# electronic_load.net
KiCad netlist of a schematic drawn in EAGLE
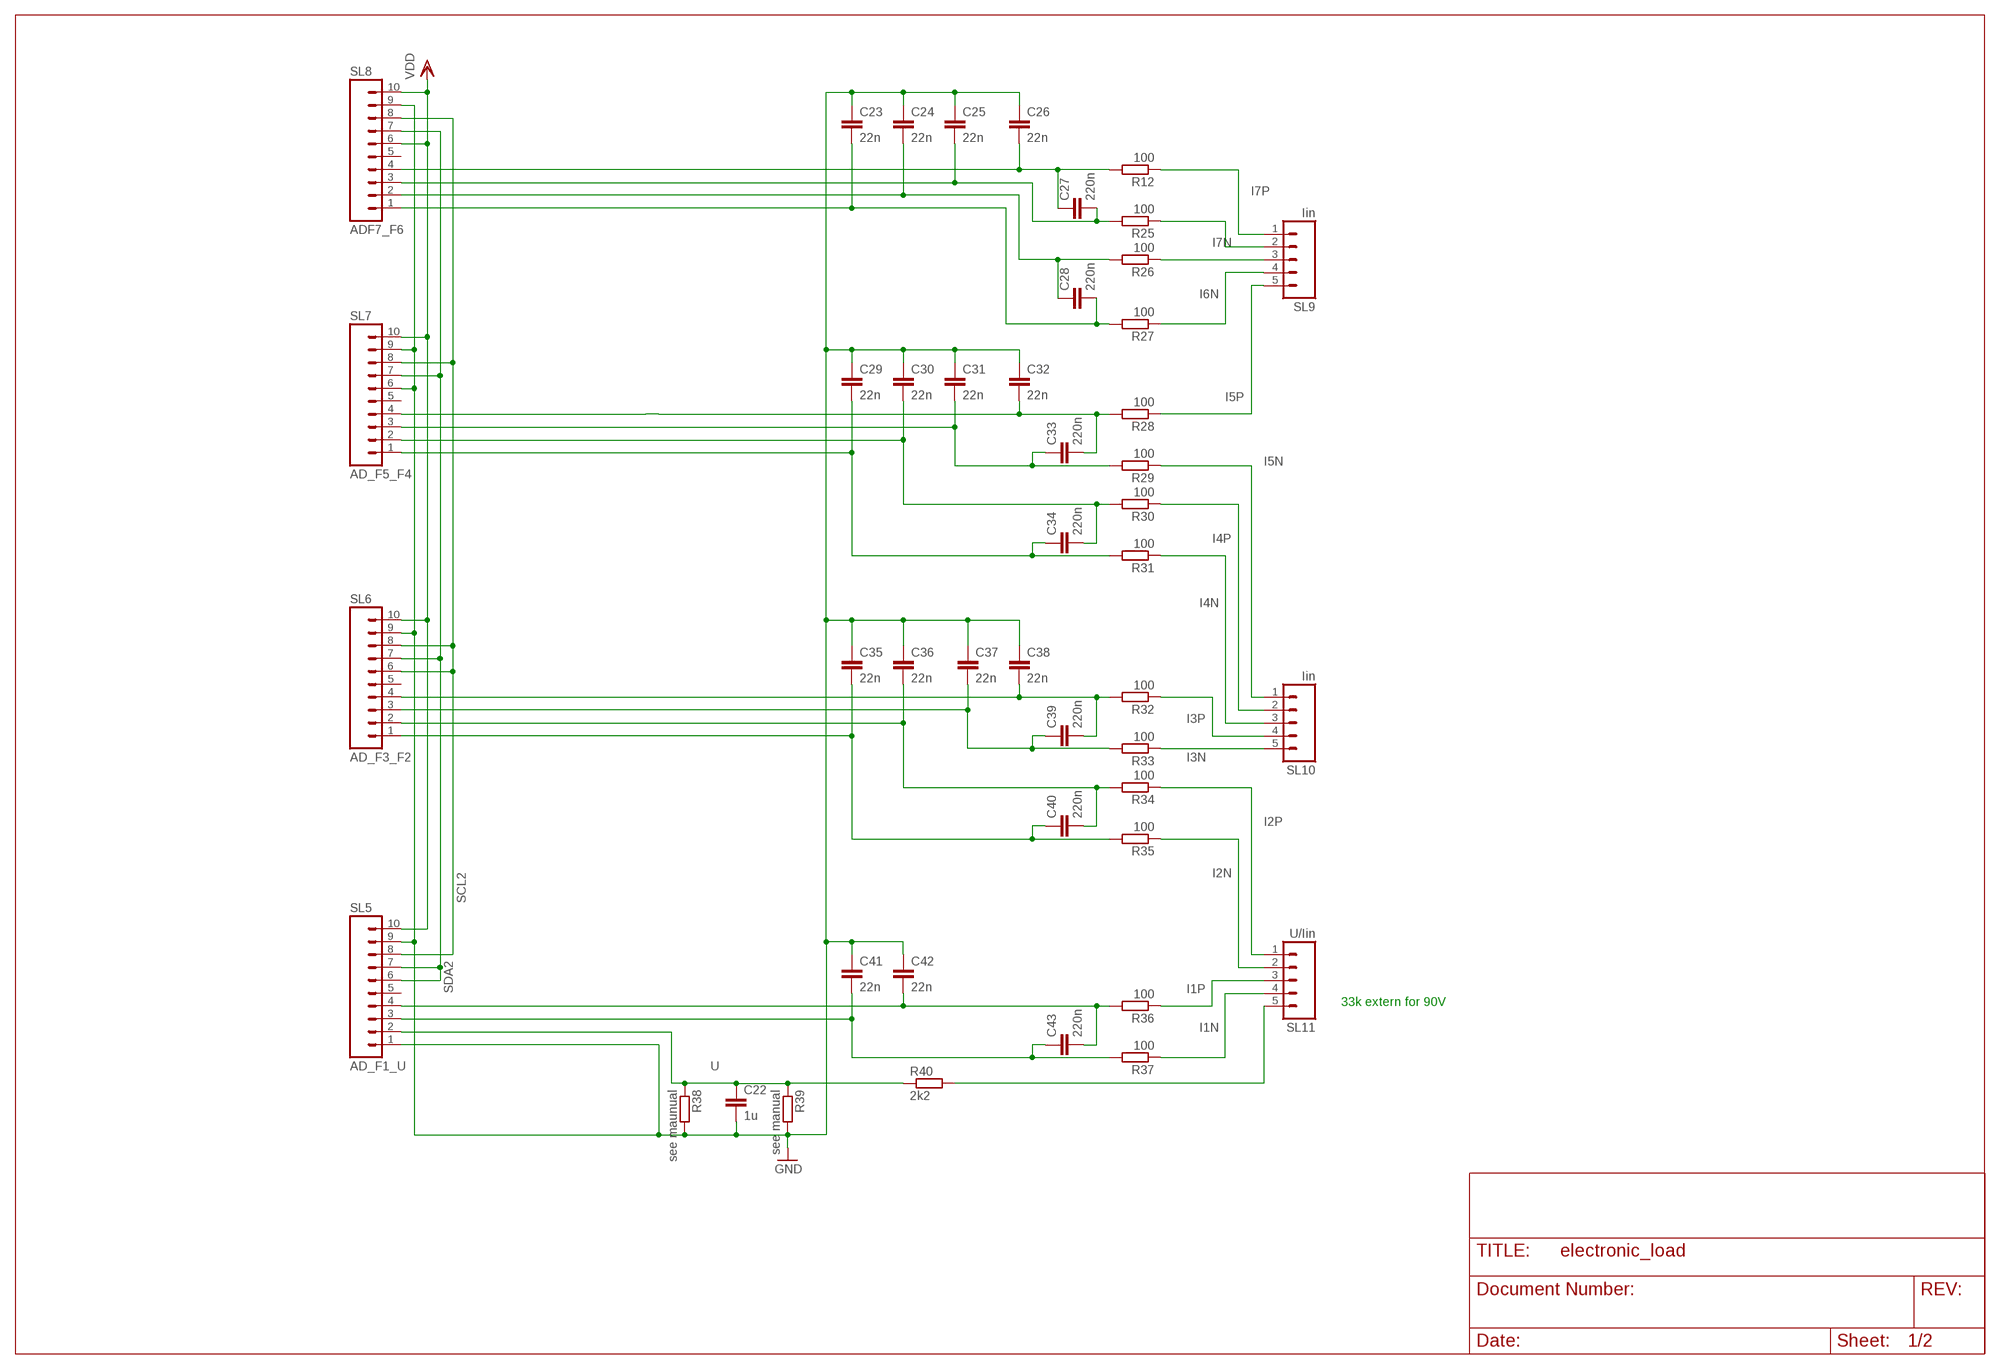
[diagram p0: schematic, sheet 1]
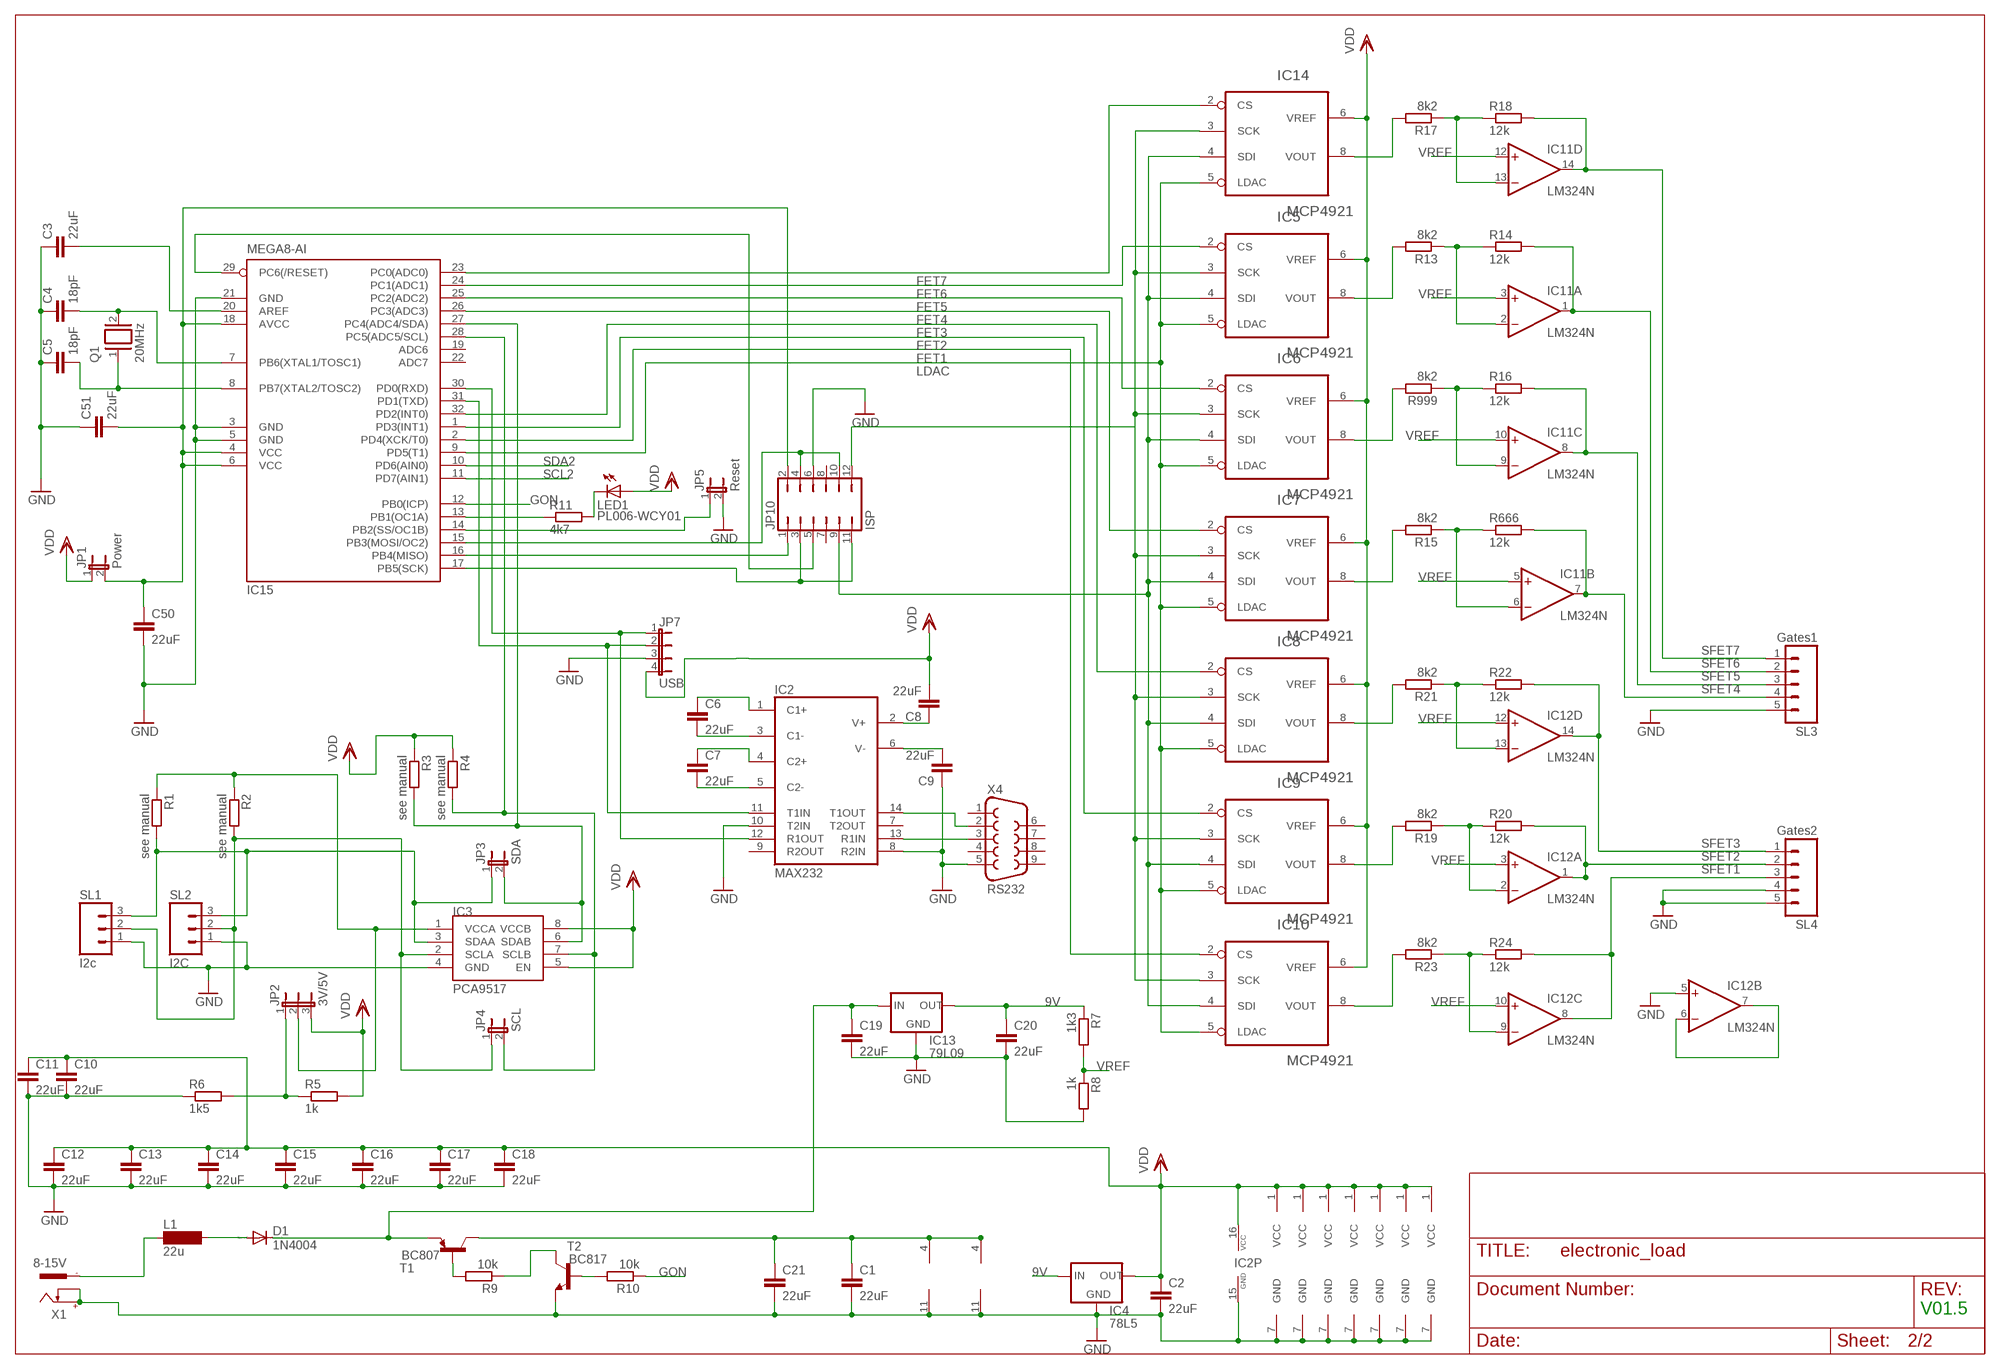
[diagram p1: schematic, sheet 2]

(export (version "E")
  (design (tool "Eeschema 10.0.6"))
  (components
    (comp (ref "C1")
      (value "22uF")
      (footprint "eagle-import:C1206")
      (libsource (lib "eagle-import") (part "C-EUC1206"))
    )
    (comp (ref "C2")
      (value "22uF")
      (footprint "eagle-import:C1206")
      (libsource (lib "eagle-import") (part "C-EUC1206"))
    )
    (comp (ref "C3")
      (value "22uF")
      (footprint "eagle-import:C1206")
      (libsource (lib "eagle-import") (part "C-EUC1206"))
    )
    (comp (ref "C4")
      (value "18pF")
      (footprint "eagle-import:C025-025X050")
      (libsource (lib "eagle-import") (part "resistor_C-EU025-025X050"))
    )
    (comp (ref "C5")
      (value "18pF")
      (footprint "eagle-import:C025-025X050")
      (libsource (lib "eagle-import") (part "resistor_C-EU025-025X050"))
    )
    (comp (ref "C6")
      (value "22uF")
      (footprint "eagle-import:C1206")
      (libsource (lib "eagle-import") (part "C-EUC1206"))
    )
    (comp (ref "C7")
      (value "22uF")
      (footprint "eagle-import:C1206")
      (libsource (lib "eagle-import") (part "C-EUC1206"))
    )
    (comp (ref "C8")
      (value "22uF")
      (footprint "eagle-import:C1206")
      (libsource (lib "eagle-import") (part "C-EUC1206"))
    )
    (comp (ref "C9")
      (value "22uF")
      (footprint "eagle-import:C1206")
      (libsource (lib "eagle-import") (part "C-EUC1206"))
    )
    (comp (ref "C10")
      (value "22uF")
      (footprint "eagle-import:C1206")
      (libsource (lib "eagle-import") (part "C-EUC1206"))
    )
    (comp (ref "C11")
      (value "22uF")
      (footprint "eagle-import:C1206")
      (libsource (lib "eagle-import") (part "C-EUC1206"))
    )
    (comp (ref "C12")
      (value "22uF")
      (footprint "eagle-import:C1206")
      (libsource (lib "eagle-import") (part "C-EUC1206"))
    )
    (comp (ref "C13")
      (value "22uF")
      (footprint "eagle-import:C1206")
      (libsource (lib "eagle-import") (part "C-EUC1206"))
    )
    (comp (ref "C14")
      (value "22uF")
      (footprint "eagle-import:C1206")
      (libsource (lib "eagle-import") (part "C-EUC1206"))
    )
    (comp (ref "C15")
      (value "22uF")
      (footprint "eagle-import:C1206")
      (libsource (lib "eagle-import") (part "C-EUC1206"))
    )
    (comp (ref "C16")
      (value "22uF")
      (footprint "eagle-import:C1206")
      (libsource (lib "eagle-import") (part "C-EUC1206"))
    )
    (comp (ref "C17")
      (value "22uF")
      (footprint "eagle-import:C1206")
      (libsource (lib "eagle-import") (part "C-EUC1206"))
    )
    (comp (ref "C18")
      (value "22uF")
      (footprint "eagle-import:C1206")
      (libsource (lib "eagle-import") (part "C-EUC1206"))
    )
    (comp (ref "C19")
      (value "22uF")
      (footprint "eagle-import:C1206")
      (libsource (lib "eagle-import") (part "C-EUC1206"))
    )
    (comp (ref "C20")
      (value "22uF")
      (footprint "eagle-import:C1206")
      (libsource (lib "eagle-import") (part "C-EUC1206"))
    )
    (comp (ref "C21")
      (value "22uF")
      (footprint "eagle-import:C1206")
      (libsource (lib "eagle-import") (part "C-EUC1206"))
    )
    (comp (ref "C50")
      (value "22uF")
      (footprint "eagle-import:C1206")
      (libsource (lib "eagle-import") (part "C-EUC1206"))
    )
    (comp (ref "C51")
      (value "22uF")
      (footprint "eagle-import:C1206")
      (libsource (lib "eagle-import") (part "C-EUC1206"))
    )
    (comp (ref "D1")
      (value "1N4004")
      (footprint "eagle-import:DO41-10")
      (libsource (lib "eagle-import") (part "1N4004"))
    )
    (comp (ref "IC2")
      (value "MAX232")
      (footprint "eagle-import:DIL16")
      (fields (field (name "MF") "MAXIM") (field (name "MPN") "MAX232ACPE+"))
      (libsource (lib "eagle-import") (part "MAX232"))
    )
    (comp (ref "IC3")
      (value "PCA9517")
      (footprint "eagle-import:SO-08")
      (libsource (lib "eagle-import") (part "PCA9517"))
    )
    (comp (ref "IC4")
      (value "78L5")
      (footprint "eagle-import:78LXX")
      (libsource (lib "eagle-import") (part "78LXX"))
    )
    (comp (ref "IC5")
      (value "MCP4921")
      (footprint "eagle-import:DIL08")
      (libsource (lib "eagle-import") (part "MCP491"))
    )
    (comp (ref "IC6")
      (value "MCP4921")
      (footprint "eagle-import:DIL08")
      (libsource (lib "eagle-import") (part "MCP491"))
    )
    (comp (ref "IC7")
      (value "MCP4921")
      (footprint "eagle-import:DIL08")
      (libsource (lib "eagle-import") (part "MCP491"))
    )
    (comp (ref "IC8")
      (value "MCP4921")
      (footprint "eagle-import:DIL08")
      (libsource (lib "eagle-import") (part "MCP491"))
    )
    (comp (ref "IC9")
      (value "MCP4921")
      (footprint "eagle-import:DIL08")
      (libsource (lib "eagle-import") (part "MCP491"))
    )
    (comp (ref "IC10")
      (value "MCP4921")
      (footprint "eagle-import:DIL08")
      (libsource (lib "eagle-import") (part "MCP491"))
    )
    (comp (ref "IC11")
      (value "LM324N")
      (footprint "eagle-import:DIL14")
      (libsource (lib "eagle-import") (part "LM324N"))
    )
    (comp (ref "IC12")
      (value "LM324N")
      (footprint "eagle-import:DIL14")
      (libsource (lib "eagle-import") (part "LM324N"))
    )
    (comp (ref "IC13")
      (value "79L09")
      (footprint "eagle-import:78LXX")
      (libsource (lib "eagle-import") (part "78LXX"))
    )
    (comp (ref "IC14")
      (value "MCP4921")
      (footprint "eagle-import:DIL08")
      (libsource (lib "eagle-import") (part "MCP491"))
    )
    (comp (ref "IC15")
      (value "MEGA8-AI")
      (footprint "eagle-import:TQFP32-08")
      (fields (field (name "MPN") "ATMEGA8-16AU"))
      (libsource (lib "eagle-import") (part "MEGA8-AI"))
    )
    (comp (ref "JP1")
      (value "Power")
      (footprint "eagle-import:JP1")
      (libsource (lib "eagle-import") (part "JP1E"))
    )
    (comp (ref "JP2")
      (value "3V/5V")
      (footprint "eagle-import:JP2")
      (libsource (lib "eagle-import") (part "JP2E"))
    )
    (comp (ref "JP3")
      (value "SDA")
      (footprint "eagle-import:JP1")
      (libsource (lib "eagle-import") (part "JP1E"))
    )
    (comp (ref "JP4")
      (value "SCL")
      (footprint "eagle-import:JP1")
      (libsource (lib "eagle-import") (part "JP1E"))
    )
    (comp (ref "JP5")
      (value "Reset")
      (footprint "eagle-import:JP1")
      (libsource (lib "eagle-import") (part "JP1E"))
    )
    (comp (ref "JP7")
      (value "USB")
      (footprint "eagle-import:JP4")
      (libsource (lib "eagle-import") (part "JP4E"))
    )
    (comp (ref "JP10")
      (value "ISP")
      (footprint "eagle-import:JP6Q")
      (libsource (lib "eagle-import") (part "JP6Q"))
    )
    (comp (ref "L1")
      (value "22u")
      (footprint "eagle-import:MS85")
      (libsource (lib "eagle-import") (part "MS85"))
    )
    (comp (ref "LED1")
      (value "PL006-WCY01")
      (footprint "eagle-import:SOT23")
      (libsource (lib "eagle-import") (part "PL006-WCY01"))
    )
    (comp (ref "Q1")
      (value "20MHz")
      (footprint "eagle-import:QS")
      (libsource (lib "eagle-import") (part "XTAL/S"))
    )
    (comp (ref "R1")
      (value "see manual")
      (footprint "eagle-import:R1206")
      (libsource (lib "eagle-import") (part "R-EU_R1206"))
    )
    (comp (ref "R2")
      (value "see manual")
      (footprint "eagle-import:R1206")
      (libsource (lib "eagle-import") (part "R-EU_R1206"))
    )
    (comp (ref "R3")
      (value "see manual")
      (footprint "eagle-import:R1206")
      (libsource (lib "eagle-import") (part "R-EU_R1206"))
    )
    (comp (ref "R4")
      (value "see manual")
      (footprint "eagle-import:R1206")
      (libsource (lib "eagle-import") (part "R-EU_R1206"))
    )
    (comp (ref "R5")
      (value "1k")
      (footprint "eagle-import:R1206")
      (libsource (lib "eagle-import") (part "R-EU_R1206"))
    )
    (comp (ref "R6")
      (value "1k5")
      (footprint "eagle-import:R1206")
      (libsource (lib "eagle-import") (part "R-EU_R1206"))
    )
    (comp (ref "R7")
      (value "1k3")
      (footprint "eagle-import:R1206")
      (libsource (lib "eagle-import") (part "R-EU_R1206"))
    )
    (comp (ref "R8")
      (value "1k")
      (footprint "eagle-import:R1206")
      (libsource (lib "eagle-import") (part "R-EU_R1206"))
    )
    (comp (ref "R9")
      (value "10k")
      (footprint "eagle-import:R1206")
      (libsource (lib "eagle-import") (part "R-EU_R1206"))
    )
    (comp (ref "R10")
      (value "10k")
      (footprint "eagle-import:R1206")
      (libsource (lib "eagle-import") (part "R-EU_R1206"))
    )
    (comp (ref "R11")
      (value "4k7")
      (footprint "eagle-import:R1206")
      (libsource (lib "eagle-import") (part "R-EU_R1206"))
    )
    (comp (ref "R13")
      (value "8k2")
      (footprint "eagle-import:R1206")
      (libsource (lib "eagle-import") (part "R-EU_R1206"))
    )
    (comp (ref "R14")
      (value "12k")
      (footprint "eagle-import:R1206")
      (libsource (lib "eagle-import") (part "R-EU_R1206"))
    )
    (comp (ref "R15")
      (value "8k2")
      (footprint "eagle-import:R1206")
      (libsource (lib "eagle-import") (part "R-EU_R1206"))
    )
    (comp (ref "R16")
      (value "12k")
      (footprint "eagle-import:R1206")
      (libsource (lib "eagle-import") (part "R-EU_R1206"))
    )
    (comp (ref "R17")
      (value "8k2")
      (footprint "eagle-import:R1206")
      (libsource (lib "eagle-import") (part "R-EU_R1206"))
    )
    (comp (ref "R18")
      (value "12k")
      (footprint "eagle-import:R1206")
      (libsource (lib "eagle-import") (part "R-EU_R1206"))
    )
    (comp (ref "R19")
      (value "8k2")
      (footprint "eagle-import:R1206")
      (libsource (lib "eagle-import") (part "R-EU_R1206"))
    )
    (comp (ref "R20")
      (value "12k")
      (footprint "eagle-import:R1206")
      (libsource (lib "eagle-import") (part "R-EU_R1206"))
    )
    (comp (ref "R21")
      (value "8k2")
      (footprint "eagle-import:R1206")
      (libsource (lib "eagle-import") (part "R-EU_R1206"))
    )
    (comp (ref "R22")
      (value "12k")
      (footprint "eagle-import:R1206")
      (libsource (lib "eagle-import") (part "R-EU_R1206"))
    )
    (comp (ref "R23")
      (value "8k2")
      (footprint "eagle-import:R1206")
      (libsource (lib "eagle-import") (part "R-EU_R1206"))
    )
    (comp (ref "R24")
      (value "12k")
      (footprint "eagle-import:R1206")
      (libsource (lib "eagle-import") (part "R-EU_R1206"))
    )
    (comp (ref "R666")
      (value "12k")
      (footprint "eagle-import:R1206")
      (libsource (lib "eagle-import") (part "R-EU_R1206"))
    )
    (comp (ref "R999")
      (value "8k2")
      (footprint "eagle-import:R1206")
      (libsource (lib "eagle-import") (part "R-EU_R1206"))
    )
    (comp (ref "SL1")
      (value "I2c")
      (footprint "eagle-import:03P")
      (libsource (lib "eagle-import") (part "M03"))
    )
    (comp (ref "SL2")
      (value "I2C")
      (footprint "eagle-import:03P")
      (libsource (lib "eagle-import") (part "M03"))
    )
    (comp (ref "SL3")
      (value "Gates1")
      (footprint "eagle-import:05P")
      (libsource (lib "eagle-import") (part "M05"))
    )
    (comp (ref "SL4")
      (value "Gates2")
      (footprint "eagle-import:05P")
      (libsource (lib "eagle-import") (part "M05"))
    )
    (comp (ref "T1")
      (value "BC807")
      (footprint "eagle-import:SOT23-BEC")
      (libsource (lib "eagle-import") (part "-PNP-SOT23-BECBC807-16"))
    )
    (comp (ref "T2")
      (value "BC817")
      (footprint "eagle-import:SOT23-BEC")
      (libsource (lib "eagle-import") (part "-NPN-SOT23-BECBC817-16"))
    )
    (comp (ref "X1")
      (value "8-15V")
      (footprint "eagle-import:737992-5")
      (libsource (lib "eagle-import") (part "737992-55"))
    )
    (comp (ref "X4")
      (value "RS232")
      (footprint "eagle-import:F09H")
      (libsource (lib "eagle-import") (part "F09H"))
    )
    (comp (ref "C22")
      (value "1u")
      (footprint "eagle-import:C1206")
      (libsource (lib "eagle-import") (part "resistor_C-EUC1206"))
    )
    (comp (ref "C23")
      (value "22n")
      (footprint "eagle-import:C1206")
      (libsource (lib "eagle-import") (part "resistor_C-EUC1206"))
    )
    (comp (ref "C24")
      (value "22n")
      (footprint "eagle-import:C1206")
      (libsource (lib "eagle-import") (part "resistor_C-EUC1206"))
    )
    (comp (ref "C25")
      (value "22n")
      (footprint "eagle-import:C1206")
      (libsource (lib "eagle-import") (part "resistor_C-EUC1206"))
    )
    (comp (ref "C26")
      (value "22n")
      (footprint "eagle-import:C1206")
      (libsource (lib "eagle-import") (part "resistor_C-EUC1206"))
    )
    (comp (ref "C27")
      (value "220n")
      (footprint "eagle-import:C1206")
      (libsource (lib "eagle-import") (part "resistor_C-EUC1206"))
    )
    (comp (ref "C28")
      (value "220n")
      (footprint "eagle-import:C1206")
      (libsource (lib "eagle-import") (part "resistor_C-EUC1206"))
    )
    (comp (ref "C29")
      (value "22n")
      (footprint "eagle-import:C1206")
      (libsource (lib "eagle-import") (part "resistor_C-EUC1206"))
    )
    (comp (ref "C30")
      (value "22n")
      (footprint "eagle-import:C1206")
      (libsource (lib "eagle-import") (part "resistor_C-EUC1206"))
    )
    (comp (ref "C31")
      (value "22n")
      (footprint "eagle-import:C1206")
      (libsource (lib "eagle-import") (part "resistor_C-EUC1206"))
    )
    (comp (ref "C32")
      (value "22n")
      (footprint "eagle-import:C1206")
      (libsource (lib "eagle-import") (part "resistor_C-EUC1206"))
    )
    (comp (ref "C33")
      (value "220n")
      (footprint "eagle-import:C1206")
      (libsource (lib "eagle-import") (part "resistor_C-EUC1206"))
    )
    (comp (ref "C34")
      (value "220n")
      (footprint "eagle-import:C1206")
      (libsource (lib "eagle-import") (part "resistor_C-EUC1206"))
    )
    (comp (ref "C35")
      (value "22n")
      (footprint "eagle-import:C1206")
      (libsource (lib "eagle-import") (part "resistor_C-EUC1206"))
    )
    (comp (ref "C36")
      (value "22n")
      (footprint "eagle-import:C1206")
      (libsource (lib "eagle-import") (part "resistor_C-EUC1206"))
    )
    (comp (ref "C37")
      (value "22n")
      (footprint "eagle-import:C1206")
      (libsource (lib "eagle-import") (part "resistor_C-EUC1206"))
    )
    (comp (ref "C38")
      (value "22n")
      (footprint "eagle-import:C1206")
      (libsource (lib "eagle-import") (part "resistor_C-EUC1206"))
    )
    (comp (ref "C39")
      (value "220n")
      (footprint "eagle-import:C1206")
      (libsource (lib "eagle-import") (part "resistor_C-EUC1206"))
    )
    (comp (ref "C40")
      (value "220n")
      (footprint "eagle-import:C1206")
      (libsource (lib "eagle-import") (part "resistor_C-EUC1206"))
    )
    (comp (ref "C41")
      (value "22n")
      (footprint "eagle-import:C1206")
      (libsource (lib "eagle-import") (part "resistor_C-EUC1206"))
    )
    (comp (ref "C42")
      (value "22n")
      (footprint "eagle-import:C1206")
      (libsource (lib "eagle-import") (part "resistor_C-EUC1206"))
    )
    (comp (ref "C43")
      (value "220n")
      (footprint "eagle-import:C1206")
      (libsource (lib "eagle-import") (part "resistor_C-EUC1206"))
    )
    (comp (ref "R12")
      (value "100")
      (footprint "eagle-import:R1206")
      (libsource (lib "eagle-import") (part "R-EU_R1206"))
    )
    (comp (ref "R25")
      (value "100")
      (footprint "eagle-import:R1206")
      (libsource (lib "eagle-import") (part "R-EU_R1206"))
    )
    (comp (ref "R26")
      (value "100")
      (footprint "eagle-import:R1206")
      (libsource (lib "eagle-import") (part "R-EU_R1206"))
    )
    (comp (ref "R27")
      (value "100")
      (footprint "eagle-import:R1206")
      (libsource (lib "eagle-import") (part "R-EU_R1206"))
    )
    (comp (ref "R28")
      (value "100")
      (footprint "eagle-import:R1206")
      (libsource (lib "eagle-import") (part "R-EU_R1206"))
    )
    (comp (ref "R29")
      (value "100")
      (footprint "eagle-import:R1206")
      (libsource (lib "eagle-import") (part "R-EU_R1206"))
    )
    (comp (ref "R30")
      (value "100")
      (footprint "eagle-import:R1206")
      (libsource (lib "eagle-import") (part "R-EU_R1206"))
    )
    (comp (ref "R31")
      (value "100")
      (footprint "eagle-import:R1206")
      (libsource (lib "eagle-import") (part "R-EU_R1206"))
    )
    (comp (ref "R32")
      (value "100")
      (footprint "eagle-import:R1206")
      (libsource (lib "eagle-import") (part "R-EU_R1206"))
    )
    (comp (ref "R33")
      (value "100")
      (footprint "eagle-import:R1206")
      (libsource (lib "eagle-import") (part "R-EU_R1206"))
    )
    (comp (ref "R34")
      (value "100")
      (footprint "eagle-import:R1206")
      (libsource (lib "eagle-import") (part "R-EU_R1206"))
    )
    (comp (ref "R35")
      (value "100")
      (footprint "eagle-import:R1206")
      (libsource (lib "eagle-import") (part "R-EU_R1206"))
    )
    (comp (ref "R36")
      (value "100")
      (footprint "eagle-import:R1206")
      (libsource (lib "eagle-import") (part "R-EU_R1206"))
    )
    (comp (ref "R37")
      (value "100")
      (footprint "eagle-import:R1206")
      (libsource (lib "eagle-import") (part "R-EU_R1206"))
    )
    (comp (ref "R38")
      (value "see maunual")
      (footprint "eagle-import:R1206")
      (libsource (lib "eagle-import") (part "R-EU_R1206"))
    )
    (comp (ref "R39")
      (value "see manual")
      (footprint "eagle-import:R1206")
      (libsource (lib "eagle-import") (part "R-EU_R1206"))
    )
    (comp (ref "R40")
      (value "2k2")
      (footprint "eagle-import:R1206")
      (libsource (lib "eagle-import") (part "R-EU_R1206"))
    )
    (comp (ref "SL5")
      (value "AD_F1_U")
      (footprint "eagle-import:10P")
      (libsource (lib "eagle-import") (part "M10"))
    )
    (comp (ref "SL6")
      (value "AD_F3_F2")
      (footprint "eagle-import:10P")
      (libsource (lib "eagle-import") (part "M10"))
    )
    (comp (ref "SL7")
      (value "AD_F5_F4")
      (footprint "eagle-import:10P")
      (libsource (lib "eagle-import") (part "M10"))
    )
    (comp (ref "SL8")
      (value "ADF7_F6")
      (footprint "eagle-import:10P")
      (libsource (lib "eagle-import") (part "M10"))
    )
    (comp (ref "SL9")
      (value "Iin")
      (footprint "eagle-import:05P")
      (libsource (lib "eagle-import") (part "M05"))
    )
    (comp (ref "SL10")
      (value "Iin")
      (footprint "eagle-import:05P")
      (libsource (lib "eagle-import") (part "M05"))
    )
    (comp (ref "SL11")
      (value "U/Iin")
      (footprint "eagle-import:05P")
      (libsource (lib "eagle-import") (part "M05"))
    )
  )
  (nets
    (net (code "1") (name "9V") (class "Default")
      (node (ref "C20") (pin "1") (pinfunction "1_1") (pintype "passive"))
      (node (ref "IC13") (pin "OUT") (pinfunction "OUT_OUT") (pintype "passive"))
      (node (ref "IC4") (pin "IN") (pinfunction "IN_IN") (pintype "input"))
      (node (ref "R7") (pin "1") (pinfunction "1_1") (pintype "passive"))
    )
    (net (code "2") (name "FET1") (class "Default")
      (node (ref "IC10") (pin "2") (pinfunction "CS_2") (pintype "input"))
      (node (ref "IC15") (pin "2") (pinfunction "PD4(XCK/T0)_2") (pintype "bidirectional"))
    )
    (net (code "3") (name "FET2") (class "Default")
      (node (ref "IC15") (pin "1") (pinfunction "PD3(INT1)_1") (pintype "bidirectional"))
      (node (ref "IC9") (pin "2") (pinfunction "CS_2") (pintype "input"))
    )
    (net (code "4") (name "FET3") (class "Default")
      (node (ref "IC15") (pin "32") (pinfunction "PD2(INT0)_32") (pintype "bidirectional"))
      (node (ref "IC8") (pin "2") (pinfunction "CS_2") (pintype "input"))
    )
    (net (code "5") (name "FET4") (class "Default")
      (node (ref "IC15") (pin "26") (pinfunction "PC3(ADC3)_26") (pintype "bidirectional"))
      (node (ref "IC7") (pin "2") (pinfunction "CS_2") (pintype "input"))
    )
    (net (code "6") (name "FET5") (class "Default")
      (node (ref "IC15") (pin "25") (pinfunction "PC2(ADC2)_25") (pintype "bidirectional"))
      (node (ref "IC6") (pin "2") (pinfunction "CS_2") (pintype "input"))
    )
    (net (code "7") (name "FET6") (class "Default")
      (node (ref "IC15") (pin "24") (pinfunction "PC1(ADC1)_24") (pintype "bidirectional"))
      (node (ref "IC5") (pin "2") (pinfunction "CS_2") (pintype "input"))
    )
    (net (code "8") (name "FET7") (class "Default")
      (node (ref "IC14") (pin "2") (pinfunction "CS_2") (pintype "input"))
      (node (ref "IC15") (pin "23") (pinfunction "PC0(ADC0)_23") (pintype "bidirectional"))
    )
    (net (code "9") (name "GND") (class "Default")
      (node (ref "C1") (pin "2") (pinfunction "2_2") (pintype "passive"))
      (node (ref "C10") (pin "2") (pinfunction "2_2") (pintype "passive"))
      (node (ref "C11") (pin "2") (pinfunction "2_2") (pintype "passive"))
      (node (ref "C12") (pin "2") (pinfunction "2_2") (pintype "passive"))
      (node (ref "C13") (pin "2") (pinfunction "2_2") (pintype "passive"))
      (node (ref "C14") (pin "2") (pinfunction "2_2") (pintype "passive"))
      (node (ref "C15") (pin "2") (pinfunction "2_2") (pintype "passive"))
      (node (ref "C16") (pin "2") (pinfunction "2_2") (pintype "passive"))
      (node (ref "C17") (pin "2") (pinfunction "2_2") (pintype "passive"))
      (node (ref "C18") (pin "2") (pinfunction "2_2") (pintype "passive"))
      (node (ref "C19") (pin "2") (pinfunction "2_2") (pintype "passive"))
      (node (ref "C2") (pin "2") (pinfunction "2_2") (pintype "passive"))
      (node (ref "C20") (pin "2") (pinfunction "2_2") (pintype "passive"))
      (node (ref "C21") (pin "2") (pinfunction "2_2") (pintype "passive"))
      (node (ref "C22") (pin "2") (pinfunction "2_2") (pintype "passive"))
      (node (ref "C23") (pin "1") (pinfunction "1_1") (pintype "passive"))
      (node (ref "C24") (pin "1") (pinfunction "1_1") (pintype "passive"))
      (node (ref "C25") (pin "1") (pinfunction "1_1") (pintype "passive"))
      (node (ref "C26") (pin "1") (pinfunction "1_1") (pintype "passive"))
      (node (ref "C29") (pin "1") (pinfunction "1_1") (pintype "passive"))
      (node (ref "C3") (pin "1") (pinfunction "1_1") (pintype "passive"))
      (node (ref "C30") (pin "1") (pinfunction "1_1") (pintype "passive"))
      (node (ref "C31") (pin "1") (pinfunction "1_1") (pintype "passive"))
      (node (ref "C32") (pin "1") (pinfunction "1_1") (pintype "passive"))
      (node (ref "C35") (pin "1") (pinfunction "1_1") (pintype "passive"))
      (node (ref "C36") (pin "1") (pinfunction "1_1") (pintype "passive"))
      (node (ref "C37") (pin "1") (pinfunction "1_1") (pintype "passive"))
      (node (ref "C38") (pin "1") (pinfunction "1_1") (pintype "passive"))
      (node (ref "C4") (pin "1") (pinfunction "1_1") (pintype "passive"))
      (node (ref "C41") (pin "1") (pinfunction "1_1") (pintype "passive"))
      (node (ref "C42") (pin "1") (pinfunction "1_1") (pintype "passive"))
      (node (ref "C5") (pin "1") (pinfunction "1_1") (pintype "passive"))
      (node (ref "C50") (pin "2") (pinfunction "2_2") (pintype "passive"))
      (node (ref "C51") (pin "1") (pinfunction "1_1") (pintype "passive"))
      (node (ref "C9") (pin "1") (pinfunction "1_1") (pintype "passive"))
      (node (ref "IC10") (pin "7") (pinfunction "GND_7") (pintype "power_in"))
      (node (ref "IC11") (pin "11") (pinfunction "V-_11") (pintype "power_in"))
      (node (ref "IC12") (pin "11") (pinfunction "V-_11") (pintype "power_in"))
      (node (ref "IC12") (pin "5") (pinfunction "+IN_5") (pintype "input"))
      (node (ref "IC13") (pin "GND") (pinfunction "GND_GND") (pintype "input"))
      (node (ref "IC14") (pin "7") (pinfunction "GND_7") (pintype "power_in"))
      (node (ref "IC15") (pin "21") (pinfunction "GND_21") (pintype "power_in"))
      (node (ref "IC15") (pin "3") (pinfunction "GND_3") (pintype "power_in"))
      (node (ref "IC15") (pin "5") (pinfunction "GND_5") (pintype "power_in"))
      (node (ref "IC2") (pin "10") (pinfunction "T2IN_10") (pintype "input"))
      (node (ref "IC2") (pin "15") (pinfunction "GND_15") (pintype "power_in"))
      (node (ref "IC2") (pin "8") (pinfunction "R2IN_8") (pintype "input"))
      (node (ref "IC3") (pin "4") (pinfunction "GND_4") (pintype "bidirectional"))
      (node (ref "IC4") (pin "GND") (pinfunction "GND_GND") (pintype "input"))
      (node (ref "IC5") (pin "7") (pinfunction "GND_7") (pintype "power_in"))
      (node (ref "IC6") (pin "7") (pinfunction "GND_7") (pintype "power_in"))
      (node (ref "IC7") (pin "7") (pinfunction "GND_7") (pintype "power_in"))
      (node (ref "IC8") (pin "7") (pinfunction "GND_7") (pintype "power_in"))
      (node (ref "IC9") (pin "7") (pinfunction "GND_7") (pintype "power_in"))
      (node (ref "JP10") (pin "6") (pinfunction "6_6") (pintype "passive"))
      (node (ref "JP5") (pin "2") (pinfunction "2_2") (pintype "passive"))
      (node (ref "JP7") (pin "3") (pinfunction "3_3") (pintype "passive"))
      (node (ref "R38") (pin "2") (pinfunction "2_2") (pintype "passive"))
      (node (ref "R39") (pin "2") (pinfunction "2_2") (pintype "passive"))
      (node (ref "R6") (pin "1") (pinfunction "1_1") (pintype "passive"))
      (node (ref "R8") (pin "2") (pinfunction "2_2") (pintype "passive"))
      (node (ref "SL1") (pin "1") (pinfunction "1_1") (pintype "passive"))
      (node (ref "SL2") (pin "1") (pinfunction "1_1") (pintype "passive"))
      (node (ref "SL3") (pin "5") (pinfunction "5_5") (pintype "passive"))
      (node (ref "SL4") (pin "4") (pinfunction "4_4") (pintype "passive"))
      (node (ref "SL4") (pin "5") (pinfunction "5_5") (pintype "passive"))
      (node (ref "SL5") (pin "1") (pinfunction "1_1") (pintype "passive"))
      (node (ref "SL5") (pin "9") (pinfunction "9_9") (pintype "passive"))
      (node (ref "SL6") (pin "9") (pinfunction "9_9") (pintype "passive"))
      (node (ref "SL7") (pin "6") (pinfunction "6_6") (pintype "passive"))
      (node (ref "SL7") (pin "9") (pinfunction "9_9") (pintype "passive"))
      (node (ref "SL8") (pin "9") (pinfunction "9_9") (pintype "passive"))
      (node (ref "T2") (pin "E") (pinfunction "E_E") (pintype "passive"))
      (node (ref "X1") (pin "+") (pinfunction "+_+") (pintype "passive"))
      (node (ref "X1") (pin "K") (pinfunction "K_K") (pintype "passive"))
      (node (ref "X4") (pin "5") (pinfunction "5_5") (pintype "passive"))
    )
    (net (code "10") (name "GON") (class "Default")
      (node (ref "IC15") (pin "12") (pinfunction "PB0(ICP)_12") (pintype "bidirectional"))
      (node (ref "R10") (pin "1") (pinfunction "1_1") (pintype "passive"))
    )
    (net (code "11") (name "I1N") (class "Default")
      (node (ref "R37") (pin "1") (pinfunction "1_1") (pintype "passive"))
      (node (ref "SL11") (pin "4") (pinfunction "4_4") (pintype "passive"))
    )
    (net (code "12") (name "I1P") (class "Default")
      (node (ref "R36") (pin "1") (pinfunction "1_1") (pintype "passive"))
      (node (ref "SL11") (pin "3") (pinfunction "3_3") (pintype "passive"))
    )
    (net (code "13") (name "I2N") (class "Default")
      (node (ref "R35") (pin "1") (pinfunction "1_1") (pintype "passive"))
      (node (ref "SL11") (pin "2") (pinfunction "2_2") (pintype "passive"))
    )
    (net (code "14") (name "I2P") (class "Default")
      (node (ref "R34") (pin "1") (pinfunction "1_1") (pintype "passive"))
      (node (ref "SL11") (pin "1") (pinfunction "1_1") (pintype "passive"))
    )
    (net (code "15") (name "I3N") (class "Default")
      (node (ref "R33") (pin "1") (pinfunction "1_1") (pintype "passive"))
      (node (ref "SL10") (pin "5") (pinfunction "5_5") (pintype "passive"))
    )
    (net (code "16") (name "I3P") (class "Default")
      (node (ref "R32") (pin "1") (pinfunction "1_1") (pintype "passive"))
      (node (ref "SL10") (pin "4") (pinfunction "4_4") (pintype "passive"))
    )
    (net (code "17") (name "I4N") (class "Default")
      (node (ref "R31") (pin "1") (pinfunction "1_1") (pintype "passive"))
      (node (ref "SL10") (pin "3") (pinfunction "3_3") (pintype "passive"))
    )
    (net (code "18") (name "I4P") (class "Default")
      (node (ref "R30") (pin "1") (pinfunction "1_1") (pintype "passive"))
      (node (ref "SL10") (pin "2") (pinfunction "2_2") (pintype "passive"))
    )
    (net (code "19") (name "I5N") (class "Default")
      (node (ref "R29") (pin "1") (pinfunction "1_1") (pintype "passive"))
      (node (ref "SL10") (pin "1") (pinfunction "1_1") (pintype "passive"))
    )
    (net (code "20") (name "I5P") (class "Default")
      (node (ref "R28") (pin "1") (pinfunction "1_1") (pintype "passive"))
      (node (ref "SL9") (pin "5") (pinfunction "5_5") (pintype "passive"))
    )
    (net (code "21") (name "I6N") (class "Default")
      (node (ref "R27") (pin "1") (pinfunction "1_1") (pintype "passive"))
      (node (ref "SL9") (pin "4") (pinfunction "4_4") (pintype "passive"))
    )
    (net (code "22") (name "I7N") (class "Default")
      (node (ref "R25") (pin "1") (pinfunction "1_1") (pintype "passive"))
      (node (ref "SL9") (pin "2") (pinfunction "2_2") (pintype "passive"))
    )
    (net (code "23") (name "I7P") (class "Default")
      (node (ref "R12") (pin "1") (pinfunction "1_1") (pintype "passive"))
      (node (ref "SL9") (pin "1") (pinfunction "1_1") (pintype "passive"))
    )
    (net (code "24") (name "LDAC") (class "Default")
      (node (ref "IC10") (pin "5") (pinfunction "LDAC_5") (pintype "input"))
      (node (ref "IC14") (pin "5") (pinfunction "LDAC_5") (pintype "input"))
      (node (ref "IC15") (pin "9") (pinfunction "PD5(T1)_9") (pintype "bidirectional"))
      (node (ref "IC5") (pin "5") (pinfunction "LDAC_5") (pintype "input"))
      (node (ref "IC6") (pin "5") (pinfunction "LDAC_5") (pintype "input"))
      (node (ref "IC7") (pin "5") (pinfunction "LDAC_5") (pintype "input"))
      (node (ref "IC8") (pin "5") (pinfunction "LDAC_5") (pintype "input"))
      (node (ref "IC9") (pin "5") (pinfunction "LDAC_5") (pintype "input"))
    )
    (net (code "25") (name "Net-(C19-Pad1)") (class "Default")
      (node (ref "C19") (pin "1") (pinfunction "1_1") (pintype "passive"))
      (node (ref "D1") (pin "C") (pinfunction "C_C") (pintype "passive"))
      (node (ref "IC13") (pin "IN") (pinfunction "IN_IN") (pintype "input"))
      (node (ref "T1") (pin "E") (pinfunction "E_E") (pintype "passive"))
    )
    (net (code "26") (name "Net-(C23-Pad2)") (class "Default")
      (node (ref "C23") (pin "2") (pinfunction "2_2") (pintype "passive"))
      (node (ref "C28") (pin "2") (pinfunction "2_2") (pintype "passive"))
      (node (ref "R27") (pin "2") (pinfunction "2_2") (pintype "passive"))
      (node (ref "SL8") (pin "1") (pinfunction "1_1") (pintype "passive"))
    )
    (net (code "27") (name "Net-(C24-Pad2)") (class "Default")
      (node (ref "C24") (pin "2") (pinfunction "2_2") (pintype "passive"))
      (node (ref "C28") (pin "1") (pinfunction "1_1") (pintype "passive"))
      (node (ref "R26") (pin "2") (pinfunction "2_2") (pintype "passive"))
      (node (ref "SL8") (pin "2") (pinfunction "2_2") (pintype "passive"))
    )
    (net (code "28") (name "Net-(C25-Pad2)") (class "Default")
      (node (ref "C25") (pin "2") (pinfunction "2_2") (pintype "passive"))
      (node (ref "C27") (pin "2") (pinfunction "2_2") (pintype "passive"))
      (node (ref "R25") (pin "2") (pinfunction "2_2") (pintype "passive"))
      (node (ref "SL8") (pin "3") (pinfunction "3_3") (pintype "passive"))
    )
    (net (code "29") (name "Net-(C26-Pad2)") (class "Default")
      (node (ref "C26") (pin "2") (pinfunction "2_2") (pintype "passive"))
      (node (ref "C27") (pin "1") (pinfunction "1_1") (pintype "passive"))
      (node (ref "R12") (pin "2") (pinfunction "2_2") (pintype "passive"))
      (node (ref "SL8") (pin "4") (pinfunction "4_4") (pintype "passive"))
    )
    (net (code "30") (name "Net-(C29-Pad2)") (class "Default")
      (node (ref "C29") (pin "2") (pinfunction "2_2") (pintype "passive"))
      (node (ref "C34") (pin "1") (pinfunction "1_1") (pintype "passive"))
      (node (ref "R31") (pin "2") (pinfunction "2_2") (pintype "passive"))
      (node (ref "SL7") (pin "1") (pinfunction "1_1") (pintype "passive"))
    )
    (net (code "31") (name "Net-(C30-Pad2)") (class "Default")
      (node (ref "C30") (pin "2") (pinfunction "2_2") (pintype "passive"))
      (node (ref "C34") (pin "2") (pinfunction "2_2") (pintype "passive"))
      (node (ref "R30") (pin "2") (pinfunction "2_2") (pintype "passive"))
      (node (ref "SL7") (pin "2") (pinfunction "2_2") (pintype "passive"))
    )
    (net (code "32") (name "Net-(C31-Pad2)") (class "Default")
      (node (ref "C31") (pin "2") (pinfunction "2_2") (pintype "passive"))
      (node (ref "C33") (pin "1") (pinfunction "1_1") (pintype "passive"))
      (node (ref "R29") (pin "2") (pinfunction "2_2") (pintype "passive"))
      (node (ref "SL7") (pin "3") (pinfunction "3_3") (pintype "passive"))
    )
    (net (code "33") (name "Net-(C32-Pad2)") (class "Default")
      (node (ref "C32") (pin "2") (pinfunction "2_2") (pintype "passive"))
      (node (ref "C33") (pin "2") (pinfunction "2_2") (pintype "passive"))
      (node (ref "R28") (pin "2") (pinfunction "2_2") (pintype "passive"))
      (node (ref "SL7") (pin "4") (pinfunction "4_4") (pintype "passive"))
    )
    (net (code "34") (name "Net-(C35-Pad2)") (class "Default")
      (node (ref "C35") (pin "2") (pinfunction "2_2") (pintype "passive"))
      (node (ref "C40") (pin "1") (pinfunction "1_1") (pintype "passive"))
      (node (ref "R35") (pin "2") (pinfunction "2_2") (pintype "passive"))
      (node (ref "SL6") (pin "1") (pinfunction "1_1") (pintype "passive"))
    )
    (net (code "35") (name "Net-(C36-Pad2)") (class "Default")
      (node (ref "C36") (pin "2") (pinfunction "2_2") (pintype "passive"))
      (node (ref "C40") (pin "2") (pinfunction "2_2") (pintype "passive"))
      (node (ref "R34") (pin "2") (pinfunction "2_2") (pintype "passive"))
      (node (ref "SL6") (pin "2") (pinfunction "2_2") (pintype "passive"))
    )
    (net (code "36") (name "Net-(C37-Pad2)") (class "Default")
      (node (ref "C37") (pin "2") (pinfunction "2_2") (pintype "passive"))
      (node (ref "C39") (pin "1") (pinfunction "1_1") (pintype "passive"))
      (node (ref "R33") (pin "2") (pinfunction "2_2") (pintype "passive"))
      (node (ref "SL6") (pin "3") (pinfunction "3_3") (pintype "passive"))
    )
    (net (code "37") (name "Net-(C38-Pad2)") (class "Default")
      (node (ref "C38") (pin "2") (pinfunction "2_2") (pintype "passive"))
      (node (ref "C39") (pin "2") (pinfunction "2_2") (pintype "passive"))
      (node (ref "R32") (pin "2") (pinfunction "2_2") (pintype "passive"))
      (node (ref "SL6") (pin "4") (pinfunction "4_4") (pintype "passive"))
    )
    (net (code "38") (name "Net-(C41-Pad2)") (class "Default")
      (node (ref "C41") (pin "2") (pinfunction "2_2") (pintype "passive"))
      (node (ref "C43") (pin "1") (pinfunction "1_1") (pintype "passive"))
      (node (ref "R37") (pin "2") (pinfunction "2_2") (pintype "passive"))
      (node (ref "SL5") (pin "3") (pinfunction "3_3") (pintype "passive"))
    )
    (net (code "39") (name "Net-(C42-Pad2)") (class "Default")
      (node (ref "C42") (pin "2") (pinfunction "2_2") (pintype "passive"))
      (node (ref "C43") (pin "2") (pinfunction "2_2") (pintype "passive"))
      (node (ref "R36") (pin "2") (pinfunction "2_2") (pintype "passive"))
      (node (ref "SL5") (pin "4") (pinfunction "4_4") (pintype "passive"))
    )
    (net (code "40") (name "Net-(D1-PadA)") (class "Default")
      (node (ref "D1") (pin "A") (pinfunction "A_A") (pintype "passive"))
      (node (ref "L1") (pin "2") (pinfunction "2_2") (pintype "passive"))
    )
    (net (code "41") (name "Net-(IC2A-C1+)") (class "Default")
      (node (ref "C6") (pin "1") (pinfunction "1_1") (pintype "passive"))
      (node (ref "IC2") (pin "1") (pinfunction "C1+_1") (pintype "bidirectional"))
    )
    (net (code "42") (name "Net-(IC2A-C1-)") (class "Default")
      (node (ref "C6") (pin "2") (pinfunction "2_2") (pintype "passive"))
      (node (ref "IC2") (pin "3") (pinfunction "C1-_3") (pintype "bidirectional"))
    )
    (net (code "43") (name "Net-(IC2A-C2+)") (class "Default")
      (node (ref "C7") (pin "1") (pinfunction "1_1") (pintype "passive"))
      (node (ref "IC2") (pin "4") (pinfunction "C2+_4") (pintype "bidirectional"))
    )
    (net (code "44") (name "Net-(IC2A-C2-)") (class "Default")
      (node (ref "C7") (pin "2") (pinfunction "2_2") (pintype "passive"))
      (node (ref "IC2") (pin "5") (pinfunction "C2-_5") (pintype "bidirectional"))
    )
    (net (code "45") (name "Net-(IC2A-R1IN)") (class "Default")
      (node (ref "IC2") (pin "13") (pinfunction "R1IN_13") (pintype "input"))
      (node (ref "X4") (pin "3") (pinfunction "3_3") (pintype "passive"))
    )
    (net (code "46") (name "Net-(IC2A-T1OUT)") (class "Default")
      (node (ref "IC2") (pin "14") (pinfunction "T1OUT_14") (pintype "output"))
      (node (ref "X4") (pin "2") (pinfunction "2_2") (pintype "passive"))
    )
    (net (code "47") (name "Net-(IC2A-V+)") (class "Default")
      (node (ref "C8") (pin "1") (pinfunction "1_1") (pintype "passive"))
      (node (ref "IC2") (pin "2") (pinfunction "V+_2") (pintype "bidirectional"))
    )
    (net (code "48") (name "Net-(IC2A-V-)") (class "Default")
      (node (ref "C9") (pin "2") (pinfunction "2_2") (pintype "passive"))
      (node (ref "IC2") (pin "6") (pinfunction "V-_6") (pintype "bidirectional"))
    )
    (net (code "49") (name "Net-(IC3-SCLA)") (class "Default")
      (node (ref "IC3") (pin "2") (pinfunction "SCLA_2") (pintype "bidirectional"))
      (node (ref "JP4") (pin "1") (pinfunction "1_1") (pintype "passive"))
      (node (ref "R2") (pin "2") (pinfunction "2_2") (pintype "passive"))
      (node (ref "SL1") (pin "2") (pinfunction "2_2") (pintype "passive"))
      (node (ref "SL2") (pin "2") (pinfunction "2_2") (pintype "passive"))
    )
    (net (code "50") (name "Net-(IC3-SDAA)") (class "Default")
      (node (ref "IC3") (pin "3") (pinfunction "SDAA_3") (pintype "bidirectional"))
      (node (ref "JP3") (pin "1") (pinfunction "1_1") (pintype "passive"))
      (node (ref "R1") (pin "2") (pinfunction "2_2") (pintype "passive"))
      (node (ref "SL1") (pin "3") (pinfunction "3_3") (pintype "passive"))
      (node (ref "SL2") (pin "3") (pinfunction "3_3") (pintype "passive"))
    )
    (net (code "51") (name "Net-(IC3-VCCA)") (class "Default")
      (node (ref "IC3") (pin "1") (pinfunction "VCCA_1") (pintype "bidirectional"))
      (node (ref "JP2") (pin "2") (pinfunction "2_2") (pintype "passive"))
      (node (ref "R1") (pin "1") (pinfunction "1_1") (pintype "passive"))
      (node (ref "R2") (pin "1") (pinfunction "1_1") (pintype "passive"))
    )
    (net (code "52") (name "Net-(IC5A-VOUT)") (class "Default")
      (node (ref "IC5") (pin "8") (pinfunction "VOUT_8") (pintype "output"))
      (node (ref "R13") (pin "2") (pinfunction "2_2") (pintype "passive"))
    )
    (net (code "53") (name "Net-(IC6A-VOUT)") (class "Default")
      (node (ref "IC6") (pin "8") (pinfunction "VOUT_8") (pintype "output"))
      (node (ref "R999") (pin "2") (pinfunction "2_2") (pintype "passive"))
    )
    (net (code "54") (name "Net-(IC7A-VOUT)") (class "Default")
      (node (ref "IC7") (pin "8") (pinfunction "VOUT_8") (pintype "output"))
      (node (ref "R15") (pin "2") (pinfunction "2_2") (pintype "passive"))
    )
    (net (code "55") (name "Net-(IC8A-VOUT)") (class "Default")
      (node (ref "IC8") (pin "8") (pinfunction "VOUT_8") (pintype "output"))
      (node (ref "R21") (pin "2") (pinfunction "2_2") (pintype "passive"))
    )
    (net (code "56") (name "Net-(IC9A-VOUT)") (class "Default")
      (node (ref "IC9") (pin "8") (pinfunction "VOUT_8") (pintype "output"))
      (node (ref "R19") (pin "2") (pinfunction "2_2") (pintype "passive"))
    )
    (net (code "57") (name "Net-(IC10A-SCK)") (class "Default")
      (node (ref "IC10") (pin "3") (pinfunction "SCK_3") (pintype "input"))
      (node (ref "IC14") (pin "3") (pinfunction "SCK_3") (pintype "input"))
      (node (ref "IC5") (pin "3") (pinfunction "SCK_3") (pintype "input"))
      (node (ref "IC6") (pin "3") (pinfunction "SCK_3") (pintype "input"))
      (node (ref "IC7") (pin "3") (pinfunction "SCK_3") (pintype "input"))
      (node (ref "IC8") (pin "3") (pinfunction "SCK_3") (pintype "input"))
      (node (ref "IC9") (pin "3") (pinfunction "SCK_3") (pintype "input"))
      (node (ref "JP10") (pin "12") (pinfunction "12_12") (pintype "passive"))
    )
    (net (code "58") (name "Net-(IC10A-SDI)") (class "Default")
      (node (ref "IC10") (pin "4") (pinfunction "SDI_4") (pintype "input"))
      (node (ref "IC14") (pin "4") (pinfunction "SDI_4") (pintype "input"))
      (node (ref "IC5") (pin "4") (pinfunction "SDI_4") (pintype "input"))
      (node (ref "IC6") (pin "4") (pinfunction "SDI_4") (pintype "input"))
      (node (ref "IC7") (pin "4") (pinfunction "SDI_4") (pintype "input"))
      (node (ref "IC8") (pin "4") (pinfunction "SDI_4") (pintype "input"))
      (node (ref "IC9") (pin "4") (pinfunction "SDI_4") (pintype "input"))
      (node (ref "JP10") (pin "9") (pinfunction "9_9") (pintype "passive"))
    )
    (net (code "59") (name "Net-(IC10A-VOUT)") (class "Default")
      (node (ref "IC10") (pin "8") (pinfunction "VOUT_8") (pintype "output"))
      (node (ref "R23") (pin "2") (pinfunction "2_2") (pintype "passive"))
    )
    (net (code "60") (name "Net-(IC11A--IN)") (class "Default")
      (node (ref "IC11") (pin "2") (pinfunction "-IN_2") (pintype "input"))
      (node (ref "R13") (pin "1") (pinfunction "1_1") (pintype "passive"))
      (node (ref "R14") (pin "1") (pinfunction "1_1") (pintype "passive"))
    )
    (net (code "61") (name "Net-(IC11B--IN)") (class "Default")
      (node (ref "IC11") (pin "6") (pinfunction "-IN_6") (pintype "input"))
      (node (ref "R15") (pin "1") (pinfunction "1_1") (pintype "passive"))
      (node (ref "R666") (pin "1") (pinfunction "1_1") (pintype "passive"))
    )
    (net (code "62") (name "Net-(IC11C--IN)") (class "Default")
      (node (ref "IC11") (pin "9") (pinfunction "-IN_9") (pintype "input"))
      (node (ref "R16") (pin "1") (pinfunction "1_1") (pintype "passive"))
      (node (ref "R999") (pin "1") (pinfunction "1_1") (pintype "passive"))
    )
    (net (code "63") (name "Net-(IC11D--IN)") (class "Default")
      (node (ref "IC11") (pin "13") (pinfunction "-IN_13") (pintype "input"))
      (node (ref "R17") (pin "1") (pinfunction "1_1") (pintype "passive"))
      (node (ref "R18") (pin "1") (pinfunction "1_1") (pintype "passive"))
    )
    (net (code "64") (name "Net-(IC11E-V+)") (class "Default")
      (node (ref "C1") (pin "1") (pinfunction "1_1") (pintype "passive"))
      (node (ref "C21") (pin "1") (pinfunction "1_1") (pintype "passive"))
      (node (ref "IC11") (pin "4") (pinfunction "V+_4") (pintype "power_in"))
      (node (ref "IC12") (pin "4") (pinfunction "V+_4") (pintype "power_in"))
      (node (ref "T1") (pin "C") (pinfunction "C_C") (pintype "passive"))
    )
    (net (code "65") (name "Net-(IC12A--IN)") (class "Default")
      (node (ref "IC12") (pin "2") (pinfunction "-IN_2") (pintype "input"))
      (node (ref "R19") (pin "1") (pinfunction "1_1") (pintype "passive"))
      (node (ref "R20") (pin "1") (pinfunction "1_1") (pintype "passive"))
    )
    (net (code "66") (name "Net-(IC12B--IN)") (class "Default")
      (node (ref "IC12") (pin "6") (pinfunction "-IN_6") (pintype "input"))
      (node (ref "IC12") (pin "7") (pinfunction "OUT_7") (pintype "output"))
    )
    (net (code "67") (name "Net-(IC12C--IN)") (class "Default")
      (node (ref "IC12") (pin "9") (pinfunction "-IN_9") (pintype "input"))
      (node (ref "R23") (pin "1") (pinfunction "1_1") (pintype "passive"))
      (node (ref "R24") (pin "1") (pinfunction "1_1") (pintype "passive"))
    )
    (net (code "68") (name "Net-(IC12D--IN)") (class "Default")
      (node (ref "IC12") (pin "13") (pinfunction "-IN_13") (pintype "input"))
      (node (ref "R21") (pin "1") (pinfunction "1_1") (pintype "passive"))
      (node (ref "R22") (pin "1") (pinfunction "1_1") (pintype "passive"))
    )
    (net (code "69") (name "Net-(IC14A-VOUT)") (class "Default")
      (node (ref "IC14") (pin "8") (pinfunction "VOUT_8") (pintype "output"))
      (node (ref "R17") (pin "2") (pinfunction "2_2") (pintype "passive"))
    )
    (net (code "70") (name "Net-(IC15-AREF)") (class "Default")
      (node (ref "C3") (pin "2") (pinfunction "2_2") (pintype "passive"))
      (node (ref "IC15") (pin "20") (pinfunction "AREF_20") (pintype "passive"))
    )
    (net (code "71") (name "Net-(IC15-AVCC)") (class "Default")
      (node (ref "C50") (pin "1") (pinfunction "1_1") (pintype "passive"))
      (node (ref "C51") (pin "2") (pinfunction "2_2") (pintype "passive"))
      (node (ref "IC15") (pin "18") (pinfunction "AVCC_18") (pintype "power_in"))
      (node (ref "IC15") (pin "4") (pinfunction "VCC_4") (pintype "power_in"))
      (node (ref "IC15") (pin "6") (pinfunction "VCC_6") (pintype "power_in"))
      (node (ref "JP1") (pin "2") (pinfunction "2_2") (pintype "passive"))
      (node (ref "JP10") (pin "2") (pinfunction "2_2") (pintype "passive"))
    )
    (net (code "72") (name "Net-(IC15-PB1(OC1A))") (class "Default")
      (node (ref "IC15") (pin "13") (pinfunction "PB1(OC1A)_13") (pintype "bidirectional"))
      (node (ref "R11") (pin "1") (pinfunction "1_1") (pintype "passive"))
    )
    (net (code "73") (name "Net-(IC15-PB2(SS{slash}OC1B))") (class "Default")
      (node (ref "IC15") (pin "14") (pinfunction "PB2(SS/OC1B)_14") (pintype "bidirectional"))
      (node (ref "JP5") (pin "1") (pinfunction "1_1") (pintype "passive"))
    )
    (net (code "74") (name "Net-(IC15-PB3(MOSI{slash}OC2))") (class "Default")
      (node (ref "IC15") (pin "15") (pinfunction "PB3(MOSI/OC2)_15") (pintype "bidirectional"))
      (node (ref "JP10") (pin "10") (pinfunction "10_10") (pintype "passive"))
      (node (ref "JP10") (pin "4") (pinfunction "4_4") (pintype "passive"))
    )
    (net (code "75") (name "Net-(IC15-PB4(MISO))") (class "Default")
      (node (ref "IC15") (pin "16") (pinfunction "PB4(MISO)_16") (pintype "bidirectional"))
      (node (ref "JP10") (pin "1") (pinfunction "1_1") (pintype "passive"))
    )
    (net (code "76") (name "Net-(IC15-PB5(SCK))") (class "Default")
      (node (ref "IC15") (pin "17") (pinfunction "PB5(SCK)_17") (pintype "bidirectional"))
      (node (ref "JP10") (pin "11") (pinfunction "11_11") (pintype "passive"))
      (node (ref "JP10") (pin "3") (pinfunction "3_3") (pintype "passive"))
    )
    (net (code "77") (name "Net-(IC15-PB6(XTAL1{slash}TOSC1))") (class "Default")
      (node (ref "C4") (pin "2") (pinfunction "2_2") (pintype "passive"))
      (node (ref "IC15") (pin "7") (pinfunction "PB6(XTAL1/TOSC1)_7") (pintype "bidirectional"))
      (node (ref "Q1") (pin "2") (pinfunction "2_2") (pintype "passive"))
    )
    (net (code "78") (name "Net-(IC15-PB7(XTAL2{slash}TOSC2))") (class "Default")
      (node (ref "C5") (pin "2") (pinfunction "2_2") (pintype "passive"))
      (node (ref "IC15") (pin "8") (pinfunction "PB7(XTAL2/TOSC2)_8") (pintype "bidirectional"))
      (node (ref "Q1") (pin "1") (pinfunction "1_1") (pintype "passive"))
    )
    (net (code "79") (name "Net-(IC15-PC4(ADC4{slash}SDA))") (class "Default")
      (node (ref "IC15") (pin "27") (pinfunction "PC4(ADC4/SDA)_27") (pintype "bidirectional"))
      (node (ref "IC3") (pin "6") (pinfunction "SDAB_6") (pintype "bidirectional"))
      (node (ref "JP3") (pin "2") (pinfunction "2_2") (pintype "passive"))
      (node (ref "R3") (pin "2") (pinfunction "2_2") (pintype "passive"))
    )
    (net (code "80") (name "Net-(IC15-PC5(ADC5{slash}SCL))") (class "Default")
      (node (ref "IC15") (pin "28") (pinfunction "PC5(ADC5/SCL)_28") (pintype "bidirectional"))
      (node (ref "IC3") (pin "7") (pinfunction "SCLB_7") (pintype "bidirectional"))
      (node (ref "JP4") (pin "2") (pinfunction "2_2") (pintype "passive"))
      (node (ref "R4") (pin "2") (pinfunction "2_2") (pintype "passive"))
    )
    (net (code "81") (name "Net-(IC15-PC6({slash}RESET))") (class "Default")
      (node (ref "IC15") (pin "29") (pinfunction "PC6(/RESET)_29") (pintype "bidirectional"))
      (node (ref "JP10") (pin "5") (pinfunction "5_5") (pintype "passive"))
    )
    (net (code "82") (name "Net-(IC15-PD0(RXD))") (class "Default")
      (node (ref "IC15") (pin "30") (pinfunction "PD0(RXD)_30") (pintype "bidirectional"))
      (node (ref "IC2") (pin "12") (pinfunction "R1OUT_12") (pintype "output"))
      (node (ref "JP7") (pin "1") (pinfunction "1_1") (pintype "passive"))
    )
    (net (code "83") (name "Net-(IC15-PD1(TXD))") (class "Default")
      (node (ref "IC15") (pin "31") (pinfunction "PD1(TXD)_31") (pintype "bidirectional"))
      (node (ref "IC2") (pin "11") (pinfunction "T1IN_11") (pintype "input"))
      (node (ref "JP7") (pin "2") (pinfunction "2_2") (pintype "passive"))
    )
    (net (code "84") (name "Net-(JP2-Pad1)") (class "Default")
      (node (ref "JP2") (pin "1") (pinfunction "1_1") (pintype "passive"))
      (node (ref "R5") (pin "1") (pinfunction "1_1") (pintype "passive"))
      (node (ref "R6") (pin "2") (pinfunction "2_2") (pintype "passive"))
    )
    (net (code "85") (name "Net-(L1-Pad1)") (class "Default")
      (node (ref "L1") (pin "1") (pinfunction "1_1") (pintype "passive"))
      (node (ref "X1") (pin "-1") (pinfunction "-1_-1") (pintype "passive"))
    )
    (net (code "86") (name "Net-(LED1-C)") (class "Default")
      (node (ref "LED1") (pin "3") (pinfunction "C_3") (pintype "passive"))
      (node (ref "R11") (pin "2") (pinfunction "2_2") (pintype "passive"))
    )
    (net (code "87") (name "Net-(R9-Pad1)") (class "Default")
      (node (ref "R9") (pin "1") (pinfunction "1_1") (pintype "passive"))
      (node (ref "T2") (pin "C") (pinfunction "C_C") (pintype "passive"))
    )
    (net (code "88") (name "Net-(R9-Pad2)") (class "Default")
      (node (ref "R9") (pin "2") (pinfunction "2_2") (pintype "passive"))
      (node (ref "T1") (pin "B") (pinfunction "B_B") (pintype "passive"))
    )
    (net (code "89") (name "Net-(R10-Pad2)") (class "Default")
      (node (ref "R10") (pin "2") (pinfunction "2_2") (pintype "passive"))
      (node (ref "T2") (pin "B") (pinfunction "B_B") (pintype "passive"))
    )
    (net (code "90") (name "Net-(R26-Pad1)") (class "Default")
      (node (ref "R26") (pin "1") (pinfunction "1_1") (pintype "passive"))
      (node (ref "SL9") (pin "3") (pinfunction "3_3") (pintype "passive"))
    )
    (net (code "91") (name "Net-(R40-Pad2)") (class "Default")
      (node (ref "R40") (pin "2") (pinfunction "2_2") (pintype "passive"))
      (node (ref "SL11") (pin "5") (pinfunction "5_5") (pintype "passive"))
    )
    (net (code "92") (name "SCL2") (class "Default")
      (node (ref "IC15") (pin "11") (pinfunction "PD7(AIN1)_11") (pintype "bidirectional"))
      (node (ref "SL5") (pin "8") (pinfunction "8_8") (pintype "passive"))
      (node (ref "SL6") (pin "6") (pinfunction "6_6") (pintype "passive"))
      (node (ref "SL6") (pin "8") (pinfunction "8_8") (pintype "passive"))
      (node (ref "SL7") (pin "8") (pinfunction "8_8") (pintype "passive"))
      (node (ref "SL8") (pin "8") (pinfunction "8_8") (pintype "passive"))
    )
    (net (code "93") (name "SDA2") (class "Default")
      (node (ref "IC15") (pin "10") (pinfunction "PD6(AIN0)_10") (pintype "bidirectional"))
      (node (ref "SL5") (pin "6") (pinfunction "6_6") (pintype "passive"))
      (node (ref "SL5") (pin "7") (pinfunction "7_7") (pintype "passive"))
      (node (ref "SL6") (pin "7") (pinfunction "7_7") (pintype "passive"))
      (node (ref "SL7") (pin "7") (pinfunction "7_7") (pintype "passive"))
      (node (ref "SL8") (pin "7") (pinfunction "7_7") (pintype "passive"))
    )
    (net (code "94") (name "SFET1") (class "Default")
      (node (ref "IC12") (pin "8") (pinfunction "OUT_8") (pintype "output"))
      (node (ref "R24") (pin "2") (pinfunction "2_2") (pintype "passive"))
      (node (ref "SL4") (pin "3") (pinfunction "3_3") (pintype "passive"))
    )
    (net (code "95") (name "SFET2") (class "Default")
      (node (ref "IC12") (pin "1") (pinfunction "OUT_1") (pintype "output"))
      (node (ref "R20") (pin "2") (pinfunction "2_2") (pintype "passive"))
      (node (ref "SL4") (pin "2") (pinfunction "2_2") (pintype "passive"))
    )
    (net (code "96") (name "SFET3") (class "Default")
      (node (ref "IC12") (pin "14") (pinfunction "OUT_14") (pintype "output"))
      (node (ref "R22") (pin "2") (pinfunction "2_2") (pintype "passive"))
      (node (ref "SL4") (pin "1") (pinfunction "1_1") (pintype "passive"))
    )
    (net (code "97") (name "SFET4") (class "Default")
      (node (ref "IC11") (pin "7") (pinfunction "OUT_7") (pintype "output"))
      (node (ref "R666") (pin "2") (pinfunction "2_2") (pintype "passive"))
      (node (ref "SL3") (pin "4") (pinfunction "4_4") (pintype "passive"))
    )
    (net (code "98") (name "SFET5") (class "Default")
      (node (ref "IC11") (pin "8") (pinfunction "OUT_8") (pintype "output"))
      (node (ref "R16") (pin "2") (pinfunction "2_2") (pintype "passive"))
      (node (ref "SL3") (pin "3") (pinfunction "3_3") (pintype "passive"))
    )
    (net (code "99") (name "SFET6") (class "Default")
      (node (ref "IC11") (pin "1") (pinfunction "OUT_1") (pintype "output"))
      (node (ref "R14") (pin "2") (pinfunction "2_2") (pintype "passive"))
      (node (ref "SL3") (pin "2") (pinfunction "2_2") (pintype "passive"))
    )
    (net (code "100") (name "SFET7") (class "Default")
      (node (ref "IC11") (pin "14") (pinfunction "OUT_14") (pintype "output"))
      (node (ref "R18") (pin "2") (pinfunction "2_2") (pintype "passive"))
      (node (ref "SL3") (pin "1") (pinfunction "1_1") (pintype "passive"))
    )
    (net (code "101") (name "U") (class "Default")
      (node (ref "C22") (pin "1") (pinfunction "1_1") (pintype "passive"))
      (node (ref "R38") (pin "1") (pinfunction "1_1") (pintype "passive"))
      (node (ref "R39") (pin "1") (pinfunction "1_1") (pintype "passive"))
      (node (ref "R40") (pin "1") (pinfunction "1_1") (pintype "passive"))
      (node (ref "SL5") (pin "2") (pinfunction "2_2") (pintype "passive"))
    )
    (net (code "102") (name "VDD") (class "Default")
      (node (ref "C10") (pin "1") (pinfunction "1_1") (pintype "passive"))
      (node (ref "C11") (pin "1") (pinfunction "1_1") (pintype "passive"))
      (node (ref "C12") (pin "1") (pinfunction "1_1") (pintype "passive"))
      (node (ref "C13") (pin "1") (pinfunction "1_1") (pintype "passive"))
      (node (ref "C14") (pin "1") (pinfunction "1_1") (pintype "passive"))
      (node (ref "C15") (pin "1") (pinfunction "1_1") (pintype "passive"))
      (node (ref "C16") (pin "1") (pinfunction "1_1") (pintype "passive"))
      (node (ref "C17") (pin "1") (pinfunction "1_1") (pintype "passive"))
      (node (ref "C18") (pin "1") (pinfunction "1_1") (pintype "passive"))
      (node (ref "C2") (pin "1") (pinfunction "1_1") (pintype "passive"))
      (node (ref "C8") (pin "2") (pinfunction "2_2") (pintype "passive"))
      (node (ref "IC10") (pin "1") (pinfunction "VCC_1") (pintype "power_in"))
      (node (ref "IC10") (pin "6") (pinfunction "VREF_6") (pintype "input"))
      (node (ref "IC14") (pin "1") (pinfunction "VCC_1") (pintype "power_in"))
      (node (ref "IC14") (pin "6") (pinfunction "VREF_6") (pintype "input"))
      (node (ref "IC2") (pin "16") (pinfunction "VCC_16") (pintype "power_in"))
      (node (ref "IC3") (pin "5") (pinfunction "EN_5") (pintype "bidirectional"))
      (node (ref "IC3") (pin "8") (pinfunction "VCCB_8") (pintype "bidirectional"))
      (node (ref "IC4") (pin "OUT") (pinfunction "OUT_OUT") (pintype "passive"))
      (node (ref "IC5") (pin "1") (pinfunction "VCC_1") (pintype "power_in"))
      (node (ref "IC5") (pin "6") (pinfunction "VREF_6") (pintype "input"))
      (node (ref "IC6") (pin "1") (pinfunction "VCC_1") (pintype "power_in"))
      (node (ref "IC6") (pin "6") (pinfunction "VREF_6") (pintype "input"))
      (node (ref "IC7") (pin "1") (pinfunction "VCC_1") (pintype "power_in"))
      (node (ref "IC7") (pin "6") (pinfunction "VREF_6") (pintype "input"))
      (node (ref "IC8") (pin "1") (pinfunction "VCC_1") (pintype "power_in"))
      (node (ref "IC8") (pin "6") (pinfunction "VREF_6") (pintype "input"))
      (node (ref "IC9") (pin "1") (pinfunction "VCC_1") (pintype "power_in"))
      (node (ref "IC9") (pin "6") (pinfunction "VREF_6") (pintype "input"))
      (node (ref "JP1") (pin "1") (pinfunction "1_1") (pintype "passive"))
      (node (ref "JP2") (pin "3") (pinfunction "3_3") (pintype "passive"))
      (node (ref "JP7") (pin "4") (pinfunction "4_4") (pintype "passive"))
      (node (ref "LED1") (pin "1") (pinfunction "A_1") (pintype "passive"))
      (node (ref "R3") (pin "1") (pinfunction "1_1") (pintype "passive"))
      (node (ref "R4") (pin "1") (pinfunction "1_1") (pintype "passive"))
      (node (ref "R5") (pin "2") (pinfunction "2_2") (pintype "passive"))
      (node (ref "SL5") (pin "10") (pinfunction "10_10") (pintype "passive"))
      (node (ref "SL6") (pin "10") (pinfunction "10_10") (pintype "passive"))
      (node (ref "SL7") (pin "10") (pinfunction "10_10") (pintype "passive"))
      (node (ref "SL8") (pin "10") (pinfunction "10_10") (pintype "passive"))
      (node (ref "SL8") (pin "6") (pinfunction "6_6") (pintype "passive"))
    )
    (net (code "103") (name "VREF") (class "Default")
      (node (ref "IC11") (pin "10") (pinfunction "+IN_10") (pintype "input"))
      (node (ref "IC11") (pin "12") (pinfunction "+IN_12") (pintype "input"))
      (node (ref "IC11") (pin "3") (pinfunction "+IN_3") (pintype "input"))
      (node (ref "IC11") (pin "5") (pinfunction "+IN_5") (pintype "input"))
      (node (ref "IC12") (pin "10") (pinfunction "+IN_10") (pintype "input"))
      (node (ref "IC12") (pin "12") (pinfunction "+IN_12") (pintype "input"))
      (node (ref "IC12") (pin "3") (pinfunction "+IN_3") (pintype "input"))
      (node (ref "R7") (pin "2") (pinfunction "2_2") (pintype "passive"))
      (node (ref "R8") (pin "1") (pinfunction "1_1") (pintype "passive"))
    )
    (net (code "104") (name "unconnected-(IC2A-R2OUT-Pad9)") (class "Default")
      (node (ref "IC2") (pin "9") (pinfunction "R2OUT_9") (pintype "output"))
    )
    (net (code "105") (name "unconnected-(IC2A-T2OUT-Pad7)") (class "Default")
      (node (ref "IC2") (pin "7") (pinfunction "T2OUT_7") (pintype "output"))
    )
    (net (code "106") (name "unconnected-(IC15-ADC6-Pad19)") (class "Default")
      (node (ref "IC15") (pin "19") (pinfunction "ADC6_19") (pintype "bidirectional"))
    )
    (net (code "107") (name "unconnected-(IC15-ADC7-Pad22)") (class "Default")
      (node (ref "IC15") (pin "22") (pinfunction "ADC7_22") (pintype "bidirectional"))
    )
    (net (code "108") (name "unconnected-(JP10-Pad7)") (class "Default")
      (node (ref "JP10") (pin "7") (pinfunction "7_7") (pintype "passive"))
    )
    (net (code "109") (name "unconnected-(JP10-Pad8)") (class "Default")
      (node (ref "JP10") (pin "8") (pinfunction "8_8") (pintype "passive"))
    )
    (net (code "110") (name "unconnected-(SL5-Pad5)") (class "Default")
      (node (ref "SL5") (pin "5") (pinfunction "5_5") (pintype "passive"))
    )
    (net (code "111") (name "unconnected-(SL6-Pad5)") (class "Default")
      (node (ref "SL6") (pin "5") (pinfunction "5_5") (pintype "passive"))
    )
    (net (code "112") (name "unconnected-(SL7-Pad5)") (class "Default")
      (node (ref "SL7") (pin "5") (pinfunction "5_5") (pintype "passive"))
    )
    (net (code "113") (name "unconnected-(SL8-Pad5)") (class "Default")
      (node (ref "SL8") (pin "5") (pinfunction "5_5") (pintype "passive"))
    )
    (net (code "114") (name "unconnected-(X1-Pad-2)") (class "Default")
      (node (ref "X1") (pin "-2") (pinfunction "-2_-2") (pintype "passive"))
    )
    (net (code "115") (name "unconnected-(X4-Pad1)") (class "Default")
      (node (ref "X4") (pin "1") (pinfunction "1_1") (pintype "passive"))
    )
    (net (code "116") (name "unconnected-(X4-Pad4)") (class "Default")
      (node (ref "X4") (pin "4") (pinfunction "4_4") (pintype "passive"))
    )
    (net (code "117") (name "unconnected-(X4-Pad6)") (class "Default")
      (node (ref "X4") (pin "6") (pinfunction "6_6") (pintype "passive"))
    )
    (net (code "118") (name "unconnected-(X4-Pad7)") (class "Default")
      (node (ref "X4") (pin "7") (pinfunction "7_7") (pintype "passive"))
    )
    (net (code "119") (name "unconnected-(X4-Pad8)") (class "Default")
      (node (ref "X4") (pin "8") (pinfunction "8_8") (pintype "passive"))
    )
    (net (code "120") (name "unconnected-(X4-Pad9)") (class "Default")
      (node (ref "X4") (pin "9") (pinfunction "9_9") (pintype "passive"))
    )
  )
)
